# W107B.net
KiCad netlist of a schematic drawn in EAGLE
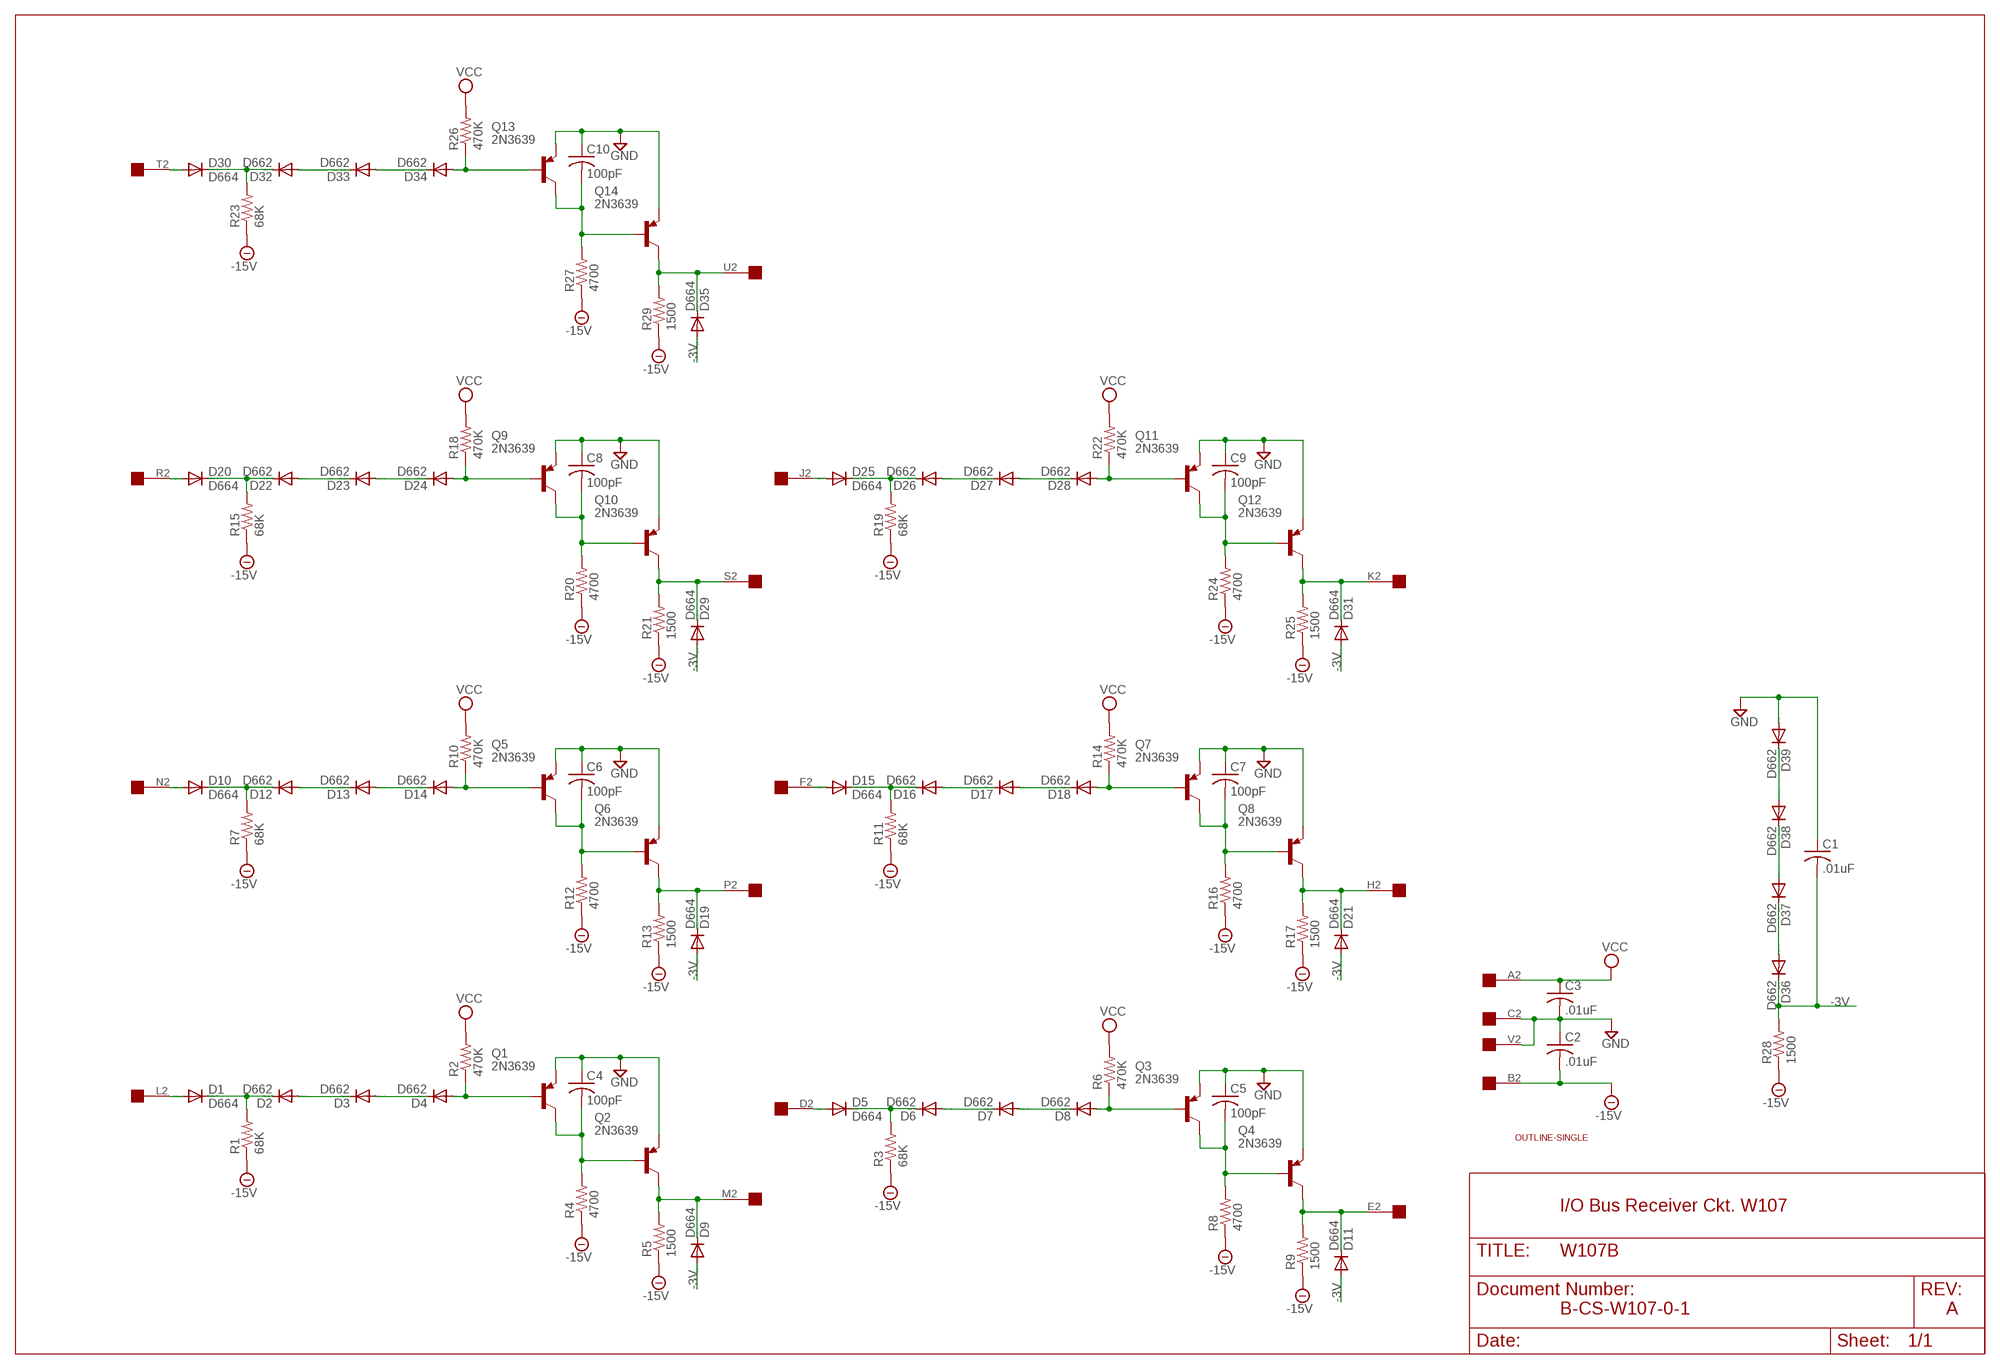
[diagram p0: schematic, sheet 1]

(export (version "E")
  (design (tool "Eeschema 10.0.6"))
  (components
    (comp (ref "C1")
      (value ".01uF")
      (footprint "eagle-import:C063-025X075")
      (libsource (lib "eagle-import") (part "C-US"))
    )
    (comp (ref "C2")
      (value ".01uF")
      (footprint "eagle-import:C063-025X075")
      (libsource (lib "eagle-import") (part "C-US"))
    )
    (comp (ref "C3")
      (value ".01uF")
      (footprint "eagle-import:C063-025X075")
      (libsource (lib "eagle-import") (part "C-US"))
    )
    (comp (ref "C4")
      (value "100pF")
      (footprint "eagle-import:C063-025X075")
      (libsource (lib "eagle-import") (part "C-US"))
    )
    (comp (ref "C5")
      (value "100pF")
      (footprint "eagle-import:C063-025X075")
      (libsource (lib "eagle-import") (part "C-US"))
    )
    (comp (ref "C6")
      (value "100pF")
      (footprint "eagle-import:C063-025X075")
      (libsource (lib "eagle-import") (part "C-US"))
    )
    (comp (ref "C7")
      (value "100pF")
      (footprint "eagle-import:C063-025X075")
      (libsource (lib "eagle-import") (part "C-US"))
    )
    (comp (ref "C8")
      (value "100pF")
      (footprint "eagle-import:C063-025X075")
      (libsource (lib "eagle-import") (part "C-US"))
    )
    (comp (ref "C9")
      (value "100pF")
      (footprint "eagle-import:C063-025X075")
      (libsource (lib "eagle-import") (part "C-US"))
    )
    (comp (ref "C10")
      (value "100pF")
      (footprint "eagle-import:C063-025X075")
      (libsource (lib "eagle-import") (part "C-US"))
    )
    (comp (ref "D1")
      (value "D664")
      (footprint "eagle-import:DO35-10")
      (libsource (lib "eagle-import") (part "DIODE-DO35-10"))
    )
    (comp (ref "D2")
      (value "D662")
      (footprint "eagle-import:DO35-10")
      (libsource (lib "eagle-import") (part "DIODE-DO35-10"))
    )
    (comp (ref "D3")
      (value "D662")
      (footprint "eagle-import:DO35-10")
      (libsource (lib "eagle-import") (part "DIODE-DO35-10"))
    )
    (comp (ref "D4")
      (value "D662")
      (footprint "eagle-import:DO35-10")
      (libsource (lib "eagle-import") (part "DIODE-DO35-10"))
    )
    (comp (ref "D5")
      (value "D664")
      (footprint "eagle-import:DO35-10")
      (libsource (lib "eagle-import") (part "DIODE-DO35-10"))
    )
    (comp (ref "D6")
      (value "D662")
      (footprint "eagle-import:DO35-10")
      (libsource (lib "eagle-import") (part "DIODE-DO35-10"))
    )
    (comp (ref "D7")
      (value "D662")
      (footprint "eagle-import:DO35-10")
      (libsource (lib "eagle-import") (part "DIODE-DO35-10"))
    )
    (comp (ref "D8")
      (value "D662")
      (footprint "eagle-import:DO35-10")
      (libsource (lib "eagle-import") (part "DIODE-DO35-10"))
    )
    (comp (ref "D9")
      (value "D664")
      (footprint "eagle-import:DO35-10")
      (libsource (lib "eagle-import") (part "DIODE-DO35-10"))
    )
    (comp (ref "D10")
      (value "D664")
      (footprint "eagle-import:DO35-10")
      (libsource (lib "eagle-import") (part "DIODE-DO35-10"))
    )
    (comp (ref "D11")
      (value "D664")
      (footprint "eagle-import:DO35-10")
      (libsource (lib "eagle-import") (part "DIODE-DO35-10"))
    )
    (comp (ref "D12")
      (value "D662")
      (footprint "eagle-import:DO35-10")
      (libsource (lib "eagle-import") (part "DIODE-DO35-10"))
    )
    (comp (ref "D13")
      (value "D662")
      (footprint "eagle-import:DO35-10")
      (libsource (lib "eagle-import") (part "DIODE-DO35-10"))
    )
    (comp (ref "D14")
      (value "D662")
      (footprint "eagle-import:DO35-10")
      (libsource (lib "eagle-import") (part "DIODE-DO35-10"))
    )
    (comp (ref "D15")
      (value "D664")
      (footprint "eagle-import:DO35-10")
      (libsource (lib "eagle-import") (part "DIODE-DO35-10"))
    )
    (comp (ref "D16")
      (value "D662")
      (footprint "eagle-import:DO35-10")
      (libsource (lib "eagle-import") (part "DIODE-DO35-10"))
    )
    (comp (ref "D17")
      (value "D662")
      (footprint "eagle-import:DO35-10")
      (libsource (lib "eagle-import") (part "DIODE-DO35-10"))
    )
    (comp (ref "D18")
      (value "D662")
      (footprint "eagle-import:DO35-10")
      (libsource (lib "eagle-import") (part "DIODE-DO35-10"))
    )
    (comp (ref "D19")
      (value "D664")
      (footprint "eagle-import:DO35-10")
      (libsource (lib "eagle-import") (part "DIODE-DO35-10"))
    )
    (comp (ref "D20")
      (value "D664")
      (footprint "eagle-import:DO35-10")
      (libsource (lib "eagle-import") (part "DIODE-DO35-10"))
    )
    (comp (ref "D21")
      (value "D664")
      (footprint "eagle-import:DO35-10")
      (libsource (lib "eagle-import") (part "DIODE-DO35-10"))
    )
    (comp (ref "D22")
      (value "D662")
      (footprint "eagle-import:DO35-10")
      (libsource (lib "eagle-import") (part "DIODE-DO35-10"))
    )
    (comp (ref "D23")
      (value "D662")
      (footprint "eagle-import:DO35-10")
      (libsource (lib "eagle-import") (part "DIODE-DO35-10"))
    )
    (comp (ref "D24")
      (value "D662")
      (footprint "eagle-import:DO35-10")
      (libsource (lib "eagle-import") (part "DIODE-DO35-10"))
    )
    (comp (ref "D25")
      (value "D664")
      (footprint "eagle-import:DO35-10")
      (libsource (lib "eagle-import") (part "DIODE-DO35-10"))
    )
    (comp (ref "D26")
      (value "D662")
      (footprint "eagle-import:DO35-10")
      (libsource (lib "eagle-import") (part "DIODE-DO35-10"))
    )
    (comp (ref "D27")
      (value "D662")
      (footprint "eagle-import:DO35-10")
      (libsource (lib "eagle-import") (part "DIODE-DO35-10"))
    )
    (comp (ref "D28")
      (value "D662")
      (footprint "eagle-import:DO35-10")
      (libsource (lib "eagle-import") (part "DIODE-DO35-10"))
    )
    (comp (ref "D29")
      (value "D664")
      (footprint "eagle-import:DO35-10")
      (libsource (lib "eagle-import") (part "DIODE-DO35-10"))
    )
    (comp (ref "D30")
      (value "D664")
      (footprint "eagle-import:DO35-10")
      (libsource (lib "eagle-import") (part "DIODE-DO35-10"))
    )
    (comp (ref "D31")
      (value "D664")
      (footprint "eagle-import:DO35-10")
      (libsource (lib "eagle-import") (part "DIODE-DO35-10"))
    )
    (comp (ref "D32")
      (value "D662")
      (footprint "eagle-import:DO35-10")
      (libsource (lib "eagle-import") (part "DIODE-DO35-10"))
    )
    (comp (ref "D33")
      (value "D662")
      (footprint "eagle-import:DO35-10")
      (libsource (lib "eagle-import") (part "DIODE-DO35-10"))
    )
    (comp (ref "D34")
      (value "D662")
      (footprint "eagle-import:DO35-10")
      (libsource (lib "eagle-import") (part "DIODE-DO35-10"))
    )
    (comp (ref "D35")
      (value "D664")
      (footprint "eagle-import:DO35-10")
      (libsource (lib "eagle-import") (part "DIODE-DO35-10"))
    )
    (comp (ref "D36")
      (value "D662")
      (footprint "eagle-import:DO35-10")
      (libsource (lib "eagle-import") (part "DIODE-DO35-10"))
    )
    (comp (ref "D37")
      (value "D662")
      (footprint "eagle-import:DO35-10")
      (libsource (lib "eagle-import") (part "DIODE-DO35-10"))
    )
    (comp (ref "D38")
      (value "D662")
      (footprint "eagle-import:DO35-10")
      (libsource (lib "eagle-import") (part "DIODE-DO35-10"))
    )
    (comp (ref "D39")
      (value "D662")
      (footprint "eagle-import:DO35-10")
      (libsource (lib "eagle-import") (part "DIODE-DO35-10"))
    )
    (comp (ref "Q1")
      (value "2N3639")
      (footprint "eagle-import:TO5")
      (libsource (lib "eagle-import") (part "-PNP-TO5"))
    )
    (comp (ref "Q2")
      (value "2N3639")
      (footprint "eagle-import:TO5")
      (libsource (lib "eagle-import") (part "-PNP-TO5"))
    )
    (comp (ref "Q3")
      (value "2N3639")
      (footprint "eagle-import:TO5")
      (libsource (lib "eagle-import") (part "-PNP-TO5"))
    )
    (comp (ref "Q4")
      (value "2N3639")
      (footprint "eagle-import:TO5")
      (libsource (lib "eagle-import") (part "-PNP-TO5"))
    )
    (comp (ref "Q5")
      (value "2N3639")
      (footprint "eagle-import:TO5")
      (libsource (lib "eagle-import") (part "-PNP-TO5"))
    )
    (comp (ref "Q6")
      (value "2N3639")
      (footprint "eagle-import:TO5")
      (libsource (lib "eagle-import") (part "-PNP-TO5"))
    )
    (comp (ref "Q7")
      (value "2N3639")
      (footprint "eagle-import:TO5")
      (libsource (lib "eagle-import") (part "-PNP-TO5"))
    )
    (comp (ref "Q8")
      (value "2N3639")
      (footprint "eagle-import:TO5")
      (libsource (lib "eagle-import") (part "-PNP-TO5"))
    )
    (comp (ref "Q9")
      (value "2N3639")
      (footprint "eagle-import:TO5")
      (libsource (lib "eagle-import") (part "-PNP-TO5"))
    )
    (comp (ref "Q10")
      (value "2N3639")
      (footprint "eagle-import:TO5")
      (libsource (lib "eagle-import") (part "-PNP-TO5"))
    )
    (comp (ref "Q11")
      (value "2N3639")
      (footprint "eagle-import:TO5")
      (libsource (lib "eagle-import") (part "-PNP-TO5"))
    )
    (comp (ref "Q12")
      (value "2N3639")
      (footprint "eagle-import:TO5")
      (libsource (lib "eagle-import") (part "-PNP-TO5"))
    )
    (comp (ref "Q13")
      (value "2N3639")
      (footprint "eagle-import:TO5")
      (libsource (lib "eagle-import") (part "-PNP-TO5"))
    )
    (comp (ref "Q14")
      (value "2N3639")
      (footprint "eagle-import:TO5")
      (libsource (lib "eagle-import") (part "-PNP-TO5"))
    )
    (comp (ref "R1")
      (value "68K")
      (footprint "eagle-import:0207_10")
      (libsource (lib "eagle-import") (part "R-US_0207/10"))
    )
    (comp (ref "R2")
      (value "470K")
      (footprint "eagle-import:0207_10")
      (libsource (lib "eagle-import") (part "R-US_0207/10"))
    )
    (comp (ref "R3")
      (value "68K")
      (footprint "eagle-import:0207_10")
      (libsource (lib "eagle-import") (part "R-US_0207/10"))
    )
    (comp (ref "R4")
      (value "4700")
      (footprint "eagle-import:0207_10")
      (libsource (lib "eagle-import") (part "R-US_0207/10"))
    )
    (comp (ref "R5")
      (value "1500")
      (footprint "eagle-import:0207_10")
      (libsource (lib "eagle-import") (part "R-US_0207/10"))
    )
    (comp (ref "R6")
      (value "470K")
      (footprint "eagle-import:0207_10")
      (libsource (lib "eagle-import") (part "R-US_0207/10"))
    )
    (comp (ref "R7")
      (value "68K")
      (footprint "eagle-import:0207_10")
      (libsource (lib "eagle-import") (part "R-US_0207/10"))
    )
    (comp (ref "R8")
      (value "4700")
      (footprint "eagle-import:0207_10")
      (libsource (lib "eagle-import") (part "R-US_0207/10"))
    )
    (comp (ref "R9")
      (value "1500")
      (footprint "eagle-import:0207_10")
      (libsource (lib "eagle-import") (part "R-US_0207/10"))
    )
    (comp (ref "R10")
      (value "470K")
      (footprint "eagle-import:0207_10")
      (libsource (lib "eagle-import") (part "R-US_0207/10"))
    )
    (comp (ref "R11")
      (value "68K")
      (footprint "eagle-import:0207_10")
      (libsource (lib "eagle-import") (part "R-US_0207/10"))
    )
    (comp (ref "R12")
      (value "4700")
      (footprint "eagle-import:0207_10")
      (libsource (lib "eagle-import") (part "R-US_0207/10"))
    )
    (comp (ref "R13")
      (value "1500")
      (footprint "eagle-import:0207_10")
      (libsource (lib "eagle-import") (part "R-US_0207/10"))
    )
    (comp (ref "R14")
      (value "470K")
      (footprint "eagle-import:0207_10")
      (libsource (lib "eagle-import") (part "R-US_0207/10"))
    )
    (comp (ref "R15")
      (value "68K")
      (footprint "eagle-import:0207_10")
      (libsource (lib "eagle-import") (part "R-US_0207/10"))
    )
    (comp (ref "R16")
      (value "4700")
      (footprint "eagle-import:0207_10")
      (libsource (lib "eagle-import") (part "R-US_0207/10"))
    )
    (comp (ref "R17")
      (value "1500")
      (footprint "eagle-import:0207_10")
      (libsource (lib "eagle-import") (part "R-US_0207/10"))
    )
    (comp (ref "R18")
      (value "470K")
      (footprint "eagle-import:0207_10")
      (libsource (lib "eagle-import") (part "R-US_0207/10"))
    )
    (comp (ref "R19")
      (value "68K")
      (footprint "eagle-import:0207_10")
      (libsource (lib "eagle-import") (part "R-US_0207/10"))
    )
    (comp (ref "R20")
      (value "4700")
      (footprint "eagle-import:0207_10")
      (libsource (lib "eagle-import") (part "R-US_0207/10"))
    )
    (comp (ref "R21")
      (value "1500")
      (footprint "eagle-import:0207_10")
      (libsource (lib "eagle-import") (part "R-US_0207/10"))
    )
    (comp (ref "R22")
      (value "470K")
      (footprint "eagle-import:0207_10")
      (libsource (lib "eagle-import") (part "R-US_0207/10"))
    )
    (comp (ref "R23")
      (value "68K")
      (footprint "eagle-import:0207_10")
      (libsource (lib "eagle-import") (part "R-US_0207/10"))
    )
    (comp (ref "R24")
      (value "4700")
      (footprint "eagle-import:0207_10")
      (libsource (lib "eagle-import") (part "R-US_0207/10"))
    )
    (comp (ref "R25")
      (value "1500")
      (footprint "eagle-import:0207_10")
      (libsource (lib "eagle-import") (part "R-US_0207/10"))
    )
    (comp (ref "R26")
      (value "470K")
      (footprint "eagle-import:0207_10")
      (libsource (lib "eagle-import") (part "R-US_0207/10"))
    )
    (comp (ref "R27")
      (value "4700")
      (footprint "eagle-import:0207_10")
      (libsource (lib "eagle-import") (part "R-US_0207/10"))
    )
    (comp (ref "R28")
      (value "1500")
      (footprint "eagle-import:0207_10")
      (libsource (lib "eagle-import") (part "R-US_0207/10"))
    )
    (comp (ref "R29")
      (value "1500")
      (footprint "eagle-import:0207_10")
      (libsource (lib "eagle-import") (part "R-US_0207/10"))
    )
    (comp (ref "U$1")
      (value "OUTLINE-SINGLE")
      (footprint "eagle-import:SINGLE")
      (libsource (lib "eagle-import") (part "OUTLINE-SINGLE"))
    )
    (comp (ref "U$2")
      (value "EDGE-1")
      (footprint "eagle-import:EDGE-CON1")
      (libsource (lib "eagle-import") (part "EDGE-1"))
    )
  )
  (nets
    (net (code "1") (name "-15V") (class "Default")
      (node (ref "C2") (pin "2") (pinfunction "2_2") (pintype "passive"))
      (node (ref "R1") (pin "1") (pinfunction "1_1") (pintype "passive"))
      (node (ref "R11") (pin "1") (pinfunction "1_1") (pintype "passive"))
      (node (ref "R12") (pin "1") (pinfunction "1_1") (pintype "passive"))
      (node (ref "R13") (pin "1") (pinfunction "1_1") (pintype "passive"))
      (node (ref "R15") (pin "1") (pinfunction "1_1") (pintype "passive"))
      (node (ref "R16") (pin "1") (pinfunction "1_1") (pintype "passive"))
      (node (ref "R17") (pin "1") (pinfunction "1_1") (pintype "passive"))
      (node (ref "R19") (pin "1") (pinfunction "1_1") (pintype "passive"))
      (node (ref "R20") (pin "1") (pinfunction "1_1") (pintype "passive"))
      (node (ref "R21") (pin "1") (pinfunction "1_1") (pintype "passive"))
      (node (ref "R23") (pin "1") (pinfunction "1_1") (pintype "passive"))
      (node (ref "R24") (pin "1") (pinfunction "1_1") (pintype "passive"))
      (node (ref "R25") (pin "1") (pinfunction "1_1") (pintype "passive"))
      (node (ref "R27") (pin "1") (pinfunction "1_1") (pintype "passive"))
      (node (ref "R28") (pin "1") (pinfunction "1_1") (pintype "passive"))
      (node (ref "R29") (pin "1") (pinfunction "1_1") (pintype "passive"))
      (node (ref "R3") (pin "1") (pinfunction "1_1") (pintype "passive"))
      (node (ref "R4") (pin "1") (pinfunction "1_1") (pintype "passive"))
      (node (ref "R5") (pin "1") (pinfunction "1_1") (pintype "passive"))
      (node (ref "R7") (pin "1") (pinfunction "1_1") (pintype "passive"))
      (node (ref "R8") (pin "1") (pinfunction "1_1") (pintype "passive"))
      (node (ref "R9") (pin "1") (pinfunction "1_1") (pintype "passive"))
      (node (ref "U$2") (pin "B2") (pinfunction "1_B2") (pintype "bidirectional"))
    )
    (net (code "2") (name "/-3V") (class "Default")
      (node (ref "C1") (pin "2") (pinfunction "2_2") (pintype "passive"))
      (node (ref "D11") (pin "A") (pinfunction "A_A") (pintype "passive"))
      (node (ref "D19") (pin "A") (pinfunction "A_A") (pintype "passive"))
      (node (ref "D21") (pin "A") (pinfunction "A_A") (pintype "passive"))
      (node (ref "D29") (pin "A") (pinfunction "A_A") (pintype "passive"))
      (node (ref "D31") (pin "A") (pinfunction "A_A") (pintype "passive"))
      (node (ref "D35") (pin "A") (pinfunction "A_A") (pintype "passive"))
      (node (ref "D36") (pin "C") (pinfunction "C_C") (pintype "passive"))
      (node (ref "D9") (pin "A") (pinfunction "A_A") (pintype "passive"))
      (node (ref "R28") (pin "2") (pinfunction "2_2") (pintype "passive"))
    )
    (net (code "3") (name "GND") (class "Default")
      (node (ref "C1") (pin "1") (pinfunction "1_1") (pintype "passive"))
      (node (ref "C10") (pin "1") (pinfunction "1_1") (pintype "passive"))
      (node (ref "C2") (pin "1") (pinfunction "1_1") (pintype "passive"))
      (node (ref "C3") (pin "2") (pinfunction "2_2") (pintype "passive"))
      (node (ref "C4") (pin "1") (pinfunction "1_1") (pintype "passive"))
      (node (ref "C5") (pin "1") (pinfunction "1_1") (pintype "passive"))
      (node (ref "C6") (pin "1") (pinfunction "1_1") (pintype "passive"))
      (node (ref "C7") (pin "1") (pinfunction "1_1") (pintype "passive"))
      (node (ref "C8") (pin "1") (pinfunction "1_1") (pintype "passive"))
      (node (ref "C9") (pin "1") (pinfunction "1_1") (pintype "passive"))
      (node (ref "D39") (pin "A") (pinfunction "A_A") (pintype "passive"))
      (node (ref "Q1") (pin "1") (pinfunction "E_1") (pintype "passive"))
      (node (ref "Q10") (pin "1") (pinfunction "E_1") (pintype "passive"))
      (node (ref "Q11") (pin "1") (pinfunction "E_1") (pintype "passive"))
      (node (ref "Q12") (pin "1") (pinfunction "E_1") (pintype "passive"))
      (node (ref "Q13") (pin "1") (pinfunction "E_1") (pintype "passive"))
      (node (ref "Q14") (pin "1") (pinfunction "E_1") (pintype "passive"))
      (node (ref "Q2") (pin "1") (pinfunction "E_1") (pintype "passive"))
      (node (ref "Q3") (pin "1") (pinfunction "E_1") (pintype "passive"))
      (node (ref "Q4") (pin "1") (pinfunction "E_1") (pintype "passive"))
      (node (ref "Q5") (pin "1") (pinfunction "E_1") (pintype "passive"))
      (node (ref "Q6") (pin "1") (pinfunction "E_1") (pintype "passive"))
      (node (ref "Q7") (pin "1") (pinfunction "E_1") (pintype "passive"))
      (node (ref "Q8") (pin "1") (pinfunction "E_1") (pintype "passive"))
      (node (ref "Q9") (pin "1") (pinfunction "E_1") (pintype "passive"))
      (node (ref "U$2") (pin "C2") (pinfunction "1_C2") (pintype "bidirectional"))
      (node (ref "U$2") (pin "V2") (pinfunction "1_V2") (pintype "bidirectional"))
    )
    (net (code "4") (name "Net-(D1-PadC)") (class "Default")
      (node (ref "D1") (pin "C") (pinfunction "C_C") (pintype "passive"))
      (node (ref "D2") (pin "C") (pinfunction "C_C") (pintype "passive"))
      (node (ref "R1") (pin "2") (pinfunction "2_2") (pintype "passive"))
    )
    (net (code "5") (name "Net-(D2-PadA)") (class "Default")
      (node (ref "D2") (pin "A") (pinfunction "A_A") (pintype "passive"))
      (node (ref "D3") (pin "C") (pinfunction "C_C") (pintype "passive"))
    )
    (net (code "6") (name "Net-(D3-PadA)") (class "Default")
      (node (ref "D3") (pin "A") (pinfunction "A_A") (pintype "passive"))
      (node (ref "D4") (pin "C") (pinfunction "C_C") (pintype "passive"))
    )
    (net (code "7") (name "Net-(D5-PadC)") (class "Default")
      (node (ref "D5") (pin "C") (pinfunction "C_C") (pintype "passive"))
      (node (ref "D6") (pin "C") (pinfunction "C_C") (pintype "passive"))
      (node (ref "R3") (pin "2") (pinfunction "2_2") (pintype "passive"))
    )
    (net (code "8") (name "Net-(D6-PadA)") (class "Default")
      (node (ref "D6") (pin "A") (pinfunction "A_A") (pintype "passive"))
      (node (ref "D7") (pin "C") (pinfunction "C_C") (pintype "passive"))
    )
    (net (code "9") (name "Net-(D7-PadA)") (class "Default")
      (node (ref "D7") (pin "A") (pinfunction "A_A") (pintype "passive"))
      (node (ref "D8") (pin "C") (pinfunction "C_C") (pintype "passive"))
    )
    (net (code "10") (name "Net-(D10-PadC)") (class "Default")
      (node (ref "D10") (pin "C") (pinfunction "C_C") (pintype "passive"))
      (node (ref "D12") (pin "C") (pinfunction "C_C") (pintype "passive"))
      (node (ref "R7") (pin "2") (pinfunction "2_2") (pintype "passive"))
    )
    (net (code "11") (name "Net-(D12-PadA)") (class "Default")
      (node (ref "D12") (pin "A") (pinfunction "A_A") (pintype "passive"))
      (node (ref "D13") (pin "C") (pinfunction "C_C") (pintype "passive"))
    )
    (net (code "12") (name "Net-(D13-PadA)") (class "Default")
      (node (ref "D13") (pin "A") (pinfunction "A_A") (pintype "passive"))
      (node (ref "D14") (pin "C") (pinfunction "C_C") (pintype "passive"))
    )
    (net (code "13") (name "Net-(D15-PadC)") (class "Default")
      (node (ref "D15") (pin "C") (pinfunction "C_C") (pintype "passive"))
      (node (ref "D16") (pin "C") (pinfunction "C_C") (pintype "passive"))
      (node (ref "R11") (pin "2") (pinfunction "2_2") (pintype "passive"))
    )
    (net (code "14") (name "Net-(D16-PadA)") (class "Default")
      (node (ref "D16") (pin "A") (pinfunction "A_A") (pintype "passive"))
      (node (ref "D17") (pin "C") (pinfunction "C_C") (pintype "passive"))
    )
    (net (code "15") (name "Net-(D17-PadA)") (class "Default")
      (node (ref "D17") (pin "A") (pinfunction "A_A") (pintype "passive"))
      (node (ref "D18") (pin "C") (pinfunction "C_C") (pintype "passive"))
    )
    (net (code "16") (name "Net-(D20-PadC)") (class "Default")
      (node (ref "D20") (pin "C") (pinfunction "C_C") (pintype "passive"))
      (node (ref "D22") (pin "C") (pinfunction "C_C") (pintype "passive"))
      (node (ref "R15") (pin "2") (pinfunction "2_2") (pintype "passive"))
    )
    (net (code "17") (name "Net-(D22-PadA)") (class "Default")
      (node (ref "D22") (pin "A") (pinfunction "A_A") (pintype "passive"))
      (node (ref "D23") (pin "C") (pinfunction "C_C") (pintype "passive"))
    )
    (net (code "18") (name "Net-(D23-PadA)") (class "Default")
      (node (ref "D23") (pin "A") (pinfunction "A_A") (pintype "passive"))
      (node (ref "D24") (pin "C") (pinfunction "C_C") (pintype "passive"))
    )
    (net (code "19") (name "Net-(D25-PadC)") (class "Default")
      (node (ref "D25") (pin "C") (pinfunction "C_C") (pintype "passive"))
      (node (ref "D26") (pin "C") (pinfunction "C_C") (pintype "passive"))
      (node (ref "R19") (pin "2") (pinfunction "2_2") (pintype "passive"))
    )
    (net (code "20") (name "Net-(D26-PadA)") (class "Default")
      (node (ref "D26") (pin "A") (pinfunction "A_A") (pintype "passive"))
      (node (ref "D27") (pin "C") (pinfunction "C_C") (pintype "passive"))
    )
    (net (code "21") (name "Net-(D27-PadA)") (class "Default")
      (node (ref "D27") (pin "A") (pinfunction "A_A") (pintype "passive"))
      (node (ref "D28") (pin "C") (pinfunction "C_C") (pintype "passive"))
    )
    (net (code "22") (name "Net-(D30-PadC)") (class "Default")
      (node (ref "D30") (pin "C") (pinfunction "C_C") (pintype "passive"))
      (node (ref "D32") (pin "C") (pinfunction "C_C") (pintype "passive"))
      (node (ref "R23") (pin "2") (pinfunction "2_2") (pintype "passive"))
    )
    (net (code "23") (name "Net-(D32-PadA)") (class "Default")
      (node (ref "D32") (pin "A") (pinfunction "A_A") (pintype "passive"))
      (node (ref "D33") (pin "C") (pinfunction "C_C") (pintype "passive"))
    )
    (net (code "24") (name "Net-(D33-PadA)") (class "Default")
      (node (ref "D33") (pin "A") (pinfunction "A_A") (pintype "passive"))
      (node (ref "D34") (pin "C") (pinfunction "C_C") (pintype "passive"))
    )
    (net (code "25") (name "Net-(D36-PadA)") (class "Default")
      (node (ref "D36") (pin "A") (pinfunction "A_A") (pintype "passive"))
      (node (ref "D37") (pin "C") (pinfunction "C_C") (pintype "passive"))
    )
    (net (code "26") (name "Net-(D37-PadA)") (class "Default")
      (node (ref "D37") (pin "A") (pinfunction "A_A") (pintype "passive"))
      (node (ref "D38") (pin "C") (pinfunction "C_C") (pintype "passive"))
    )
    (net (code "27") (name "Net-(D38-PadA)") (class "Default")
      (node (ref "D38") (pin "A") (pinfunction "A_A") (pintype "passive"))
      (node (ref "D39") (pin "C") (pinfunction "C_C") (pintype "passive"))
    )
    (net (code "28") (name "Net-(Q1-B)") (class "Default")
      (node (ref "D4") (pin "A") (pinfunction "A_A") (pintype "passive"))
      (node (ref "Q1") (pin "2") (pinfunction "B_2") (pintype "passive"))
      (node (ref "R2") (pin "1") (pinfunction "1_1") (pintype "passive"))
    )
    (net (code "29") (name "Net-(Q1-C)") (class "Default")
      (node (ref "C4") (pin "2") (pinfunction "2_2") (pintype "passive"))
      (node (ref "Q1") (pin "3") (pinfunction "C_3") (pintype "passive"))
      (node (ref "Q2") (pin "2") (pinfunction "B_2") (pintype "passive"))
      (node (ref "R4") (pin "2") (pinfunction "2_2") (pintype "passive"))
    )
    (net (code "30") (name "Net-(Q2-C)") (class "Default")
      (node (ref "D9") (pin "C") (pinfunction "C_C") (pintype "passive"))
      (node (ref "Q2") (pin "3") (pinfunction "C_3") (pintype "passive"))
      (node (ref "R5") (pin "2") (pinfunction "2_2") (pintype "passive"))
      (node (ref "U$2") (pin "M2") (pinfunction "1_M2") (pintype "bidirectional"))
    )
    (net (code "31") (name "Net-(Q3-B)") (class "Default")
      (node (ref "D8") (pin "A") (pinfunction "A_A") (pintype "passive"))
      (node (ref "Q3") (pin "2") (pinfunction "B_2") (pintype "passive"))
      (node (ref "R6") (pin "1") (pinfunction "1_1") (pintype "passive"))
    )
    (net (code "32") (name "Net-(Q3-C)") (class "Default")
      (node (ref "C5") (pin "2") (pinfunction "2_2") (pintype "passive"))
      (node (ref "Q3") (pin "3") (pinfunction "C_3") (pintype "passive"))
      (node (ref "Q4") (pin "2") (pinfunction "B_2") (pintype "passive"))
      (node (ref "R8") (pin "2") (pinfunction "2_2") (pintype "passive"))
    )
    (net (code "33") (name "Net-(Q4-C)") (class "Default")
      (node (ref "D11") (pin "C") (pinfunction "C_C") (pintype "passive"))
      (node (ref "Q4") (pin "3") (pinfunction "C_3") (pintype "passive"))
      (node (ref "R9") (pin "2") (pinfunction "2_2") (pintype "passive"))
      (node (ref "U$2") (pin "E2") (pinfunction "1_E2") (pintype "bidirectional"))
    )
    (net (code "34") (name "Net-(Q5-B)") (class "Default")
      (node (ref "D14") (pin "A") (pinfunction "A_A") (pintype "passive"))
      (node (ref "Q5") (pin "2") (pinfunction "B_2") (pintype "passive"))
      (node (ref "R10") (pin "1") (pinfunction "1_1") (pintype "passive"))
    )
    (net (code "35") (name "Net-(Q5-C)") (class "Default")
      (node (ref "C6") (pin "2") (pinfunction "2_2") (pintype "passive"))
      (node (ref "Q5") (pin "3") (pinfunction "C_3") (pintype "passive"))
      (node (ref "Q6") (pin "2") (pinfunction "B_2") (pintype "passive"))
      (node (ref "R12") (pin "2") (pinfunction "2_2") (pintype "passive"))
    )
    (net (code "36") (name "Net-(Q6-C)") (class "Default")
      (node (ref "D19") (pin "C") (pinfunction "C_C") (pintype "passive"))
      (node (ref "Q6") (pin "3") (pinfunction "C_3") (pintype "passive"))
      (node (ref "R13") (pin "2") (pinfunction "2_2") (pintype "passive"))
      (node (ref "U$2") (pin "P2") (pinfunction "1_P2") (pintype "bidirectional"))
    )
    (net (code "37") (name "Net-(Q7-B)") (class "Default")
      (node (ref "D18") (pin "A") (pinfunction "A_A") (pintype "passive"))
      (node (ref "Q7") (pin "2") (pinfunction "B_2") (pintype "passive"))
      (node (ref "R14") (pin "1") (pinfunction "1_1") (pintype "passive"))
    )
    (net (code "38") (name "Net-(Q7-C)") (class "Default")
      (node (ref "C7") (pin "2") (pinfunction "2_2") (pintype "passive"))
      (node (ref "Q7") (pin "3") (pinfunction "C_3") (pintype "passive"))
      (node (ref "Q8") (pin "2") (pinfunction "B_2") (pintype "passive"))
      (node (ref "R16") (pin "2") (pinfunction "2_2") (pintype "passive"))
    )
    (net (code "39") (name "Net-(Q8-C)") (class "Default")
      (node (ref "D21") (pin "C") (pinfunction "C_C") (pintype "passive"))
      (node (ref "Q8") (pin "3") (pinfunction "C_3") (pintype "passive"))
      (node (ref "R17") (pin "2") (pinfunction "2_2") (pintype "passive"))
      (node (ref "U$2") (pin "H2") (pinfunction "1_H2") (pintype "bidirectional"))
    )
    (net (code "40") (name "Net-(Q9-B)") (class "Default")
      (node (ref "D24") (pin "A") (pinfunction "A_A") (pintype "passive"))
      (node (ref "Q9") (pin "2") (pinfunction "B_2") (pintype "passive"))
      (node (ref "R18") (pin "1") (pinfunction "1_1") (pintype "passive"))
    )
    (net (code "41") (name "Net-(Q10-B)") (class "Default")
      (node (ref "C8") (pin "2") (pinfunction "2_2") (pintype "passive"))
      (node (ref "Q10") (pin "2") (pinfunction "B_2") (pintype "passive"))
      (node (ref "Q9") (pin "3") (pinfunction "C_3") (pintype "passive"))
      (node (ref "R20") (pin "2") (pinfunction "2_2") (pintype "passive"))
    )
    (net (code "42") (name "Net-(Q10-C)") (class "Default")
      (node (ref "D29") (pin "C") (pinfunction "C_C") (pintype "passive"))
      (node (ref "Q10") (pin "3") (pinfunction "C_3") (pintype "passive"))
      (node (ref "R21") (pin "2") (pinfunction "2_2") (pintype "passive"))
      (node (ref "U$2") (pin "S2") (pinfunction "1_S2") (pintype "bidirectional"))
    )
    (net (code "43") (name "Net-(Q11-B)") (class "Default")
      (node (ref "D28") (pin "A") (pinfunction "A_A") (pintype "passive"))
      (node (ref "Q11") (pin "2") (pinfunction "B_2") (pintype "passive"))
      (node (ref "R22") (pin "1") (pinfunction "1_1") (pintype "passive"))
    )
    (net (code "44") (name "Net-(Q11-C)") (class "Default")
      (node (ref "C9") (pin "2") (pinfunction "2_2") (pintype "passive"))
      (node (ref "Q11") (pin "3") (pinfunction "C_3") (pintype "passive"))
      (node (ref "Q12") (pin "2") (pinfunction "B_2") (pintype "passive"))
      (node (ref "R24") (pin "2") (pinfunction "2_2") (pintype "passive"))
    )
    (net (code "45") (name "Net-(Q12-C)") (class "Default")
      (node (ref "D31") (pin "C") (pinfunction "C_C") (pintype "passive"))
      (node (ref "Q12") (pin "3") (pinfunction "C_3") (pintype "passive"))
      (node (ref "R25") (pin "2") (pinfunction "2_2") (pintype "passive"))
      (node (ref "U$2") (pin "K2") (pinfunction "1_K2") (pintype "bidirectional"))
    )
    (net (code "46") (name "Net-(Q13-B)") (class "Default")
      (node (ref "D34") (pin "A") (pinfunction "A_A") (pintype "passive"))
      (node (ref "Q13") (pin "2") (pinfunction "B_2") (pintype "passive"))
      (node (ref "R26") (pin "1") (pinfunction "1_1") (pintype "passive"))
    )
    (net (code "47") (name "Net-(Q13-C)") (class "Default")
      (node (ref "C10") (pin "2") (pinfunction "2_2") (pintype "passive"))
      (node (ref "Q13") (pin "3") (pinfunction "C_3") (pintype "passive"))
      (node (ref "Q14") (pin "2") (pinfunction "B_2") (pintype "passive"))
      (node (ref "R27") (pin "2") (pinfunction "2_2") (pintype "passive"))
    )
    (net (code "48") (name "Net-(Q14-C)") (class "Default")
      (node (ref "D35") (pin "C") (pinfunction "C_C") (pintype "passive"))
      (node (ref "Q14") (pin "3") (pinfunction "C_3") (pintype "passive"))
      (node (ref "R29") (pin "2") (pinfunction "2_2") (pintype "passive"))
      (node (ref "U$2") (pin "U2") (pinfunction "1_U2") (pintype "bidirectional"))
    )
    (net (code "49") (name "Net-(U$2D-1)") (class "Default")
      (node (ref "D5") (pin "A") (pinfunction "A_A") (pintype "passive"))
      (node (ref "U$2") (pin "D2") (pinfunction "1_D2") (pintype "bidirectional"))
    )
    (net (code "50") (name "Net-(U$2F-1)") (class "Default")
      (node (ref "D15") (pin "A") (pinfunction "A_A") (pintype "passive"))
      (node (ref "U$2") (pin "F2") (pinfunction "1_F2") (pintype "bidirectional"))
    )
    (net (code "51") (name "Net-(U$2H-1)") (class "Default")
      (node (ref "D25") (pin "A") (pinfunction "A_A") (pintype "passive"))
      (node (ref "U$2") (pin "J2") (pinfunction "1_J2") (pintype "bidirectional"))
    )
    (net (code "52") (name "Net-(U$2J-1)") (class "Default")
      (node (ref "D1") (pin "A") (pinfunction "A_A") (pintype "passive"))
      (node (ref "U$2") (pin "L2") (pinfunction "1_L2") (pintype "bidirectional"))
    )
    (net (code "53") (name "Net-(U$2L-1)") (class "Default")
      (node (ref "D10") (pin "A") (pinfunction "A_A") (pintype "passive"))
      (node (ref "U$2") (pin "N2") (pinfunction "1_N2") (pintype "bidirectional"))
    )
    (net (code "54") (name "Net-(U$2N-1)") (class "Default")
      (node (ref "D20") (pin "A") (pinfunction "A_A") (pintype "passive"))
      (node (ref "U$2") (pin "R2") (pinfunction "1_R2") (pintype "bidirectional"))
    )
    (net (code "55") (name "Net-(U$2P-1)") (class "Default")
      (node (ref "D30") (pin "A") (pinfunction "A_A") (pintype "passive"))
      (node (ref "U$2") (pin "T2") (pinfunction "1_T2") (pintype "bidirectional"))
    )
    (net (code "56") (name "VCC") (class "Default")
      (node (ref "C3") (pin "1") (pinfunction "1_1") (pintype "passive"))
      (node (ref "R10") (pin "2") (pinfunction "2_2") (pintype "passive"))
      (node (ref "R14") (pin "2") (pinfunction "2_2") (pintype "passive"))
      (node (ref "R18") (pin "2") (pinfunction "2_2") (pintype "passive"))
      (node (ref "R2") (pin "2") (pinfunction "2_2") (pintype "passive"))
      (node (ref "R22") (pin "2") (pinfunction "2_2") (pintype "passive"))
      (node (ref "R26") (pin "2") (pinfunction "2_2") (pintype "passive"))
      (node (ref "R6") (pin "2") (pinfunction "2_2") (pintype "passive"))
      (node (ref "U$2") (pin "A2") (pinfunction "1_A2") (pintype "bidirectional"))
    )
  )
)
